# I3C_Slaves.net
KiCad netlist of a schematic drawn in Altium Designer
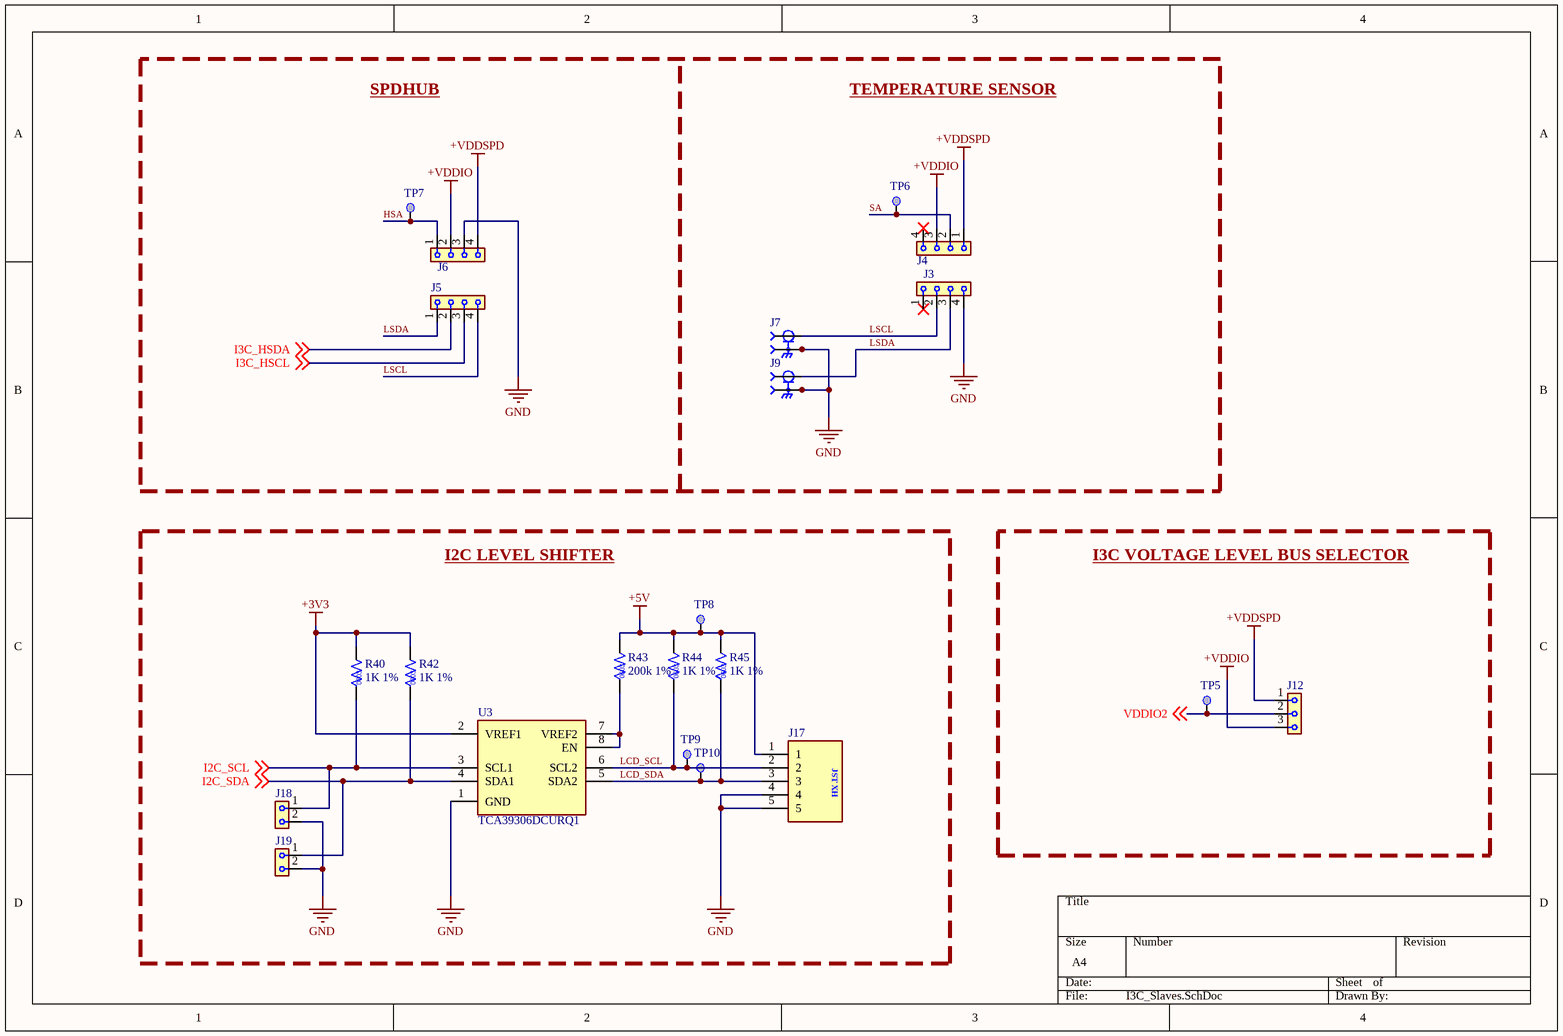
[diagram p0: I3C_Slaves.SchDoc]

(export (version "E")
  (design (tool "Eeschema 10.0.6"))
  (components
    (comp (ref "J3")
      (value "61300411821")
      (footprint "61300411821")
      (description "2.54mm Scket Header 4 pins")
      (fields (field (name "MANUFACTURER") "Wurth Elektronik"))
      (libsource (lib "DDR5_Nucleo_Shield_Symbols") (part "61300411821"))
    )
    (comp (ref "J4")
      (value "61300411821")
      (footprint "61300411821")
      (description "2.54mm Scket Header 4 pins")
      (fields (field (name "MANUFACTURER") "Wurth Elektronik"))
      (libsource (lib "") (part "61300411821_2"))
    )
    (comp (ref "J5")
      (value "61300411821")
      (footprint "61300411821")
      (description "2.54mm Scket Header 4 pins")
      (fields (field (name "MANUFACTURER") "Wurth Elektronik"))
      (libsource (lib "DDR5_Nucleo_Shield_Symbols") (part "61300411821"))
    )
    (comp (ref "J6")
      (value "61300411821")
      (footprint "61300411821")
      (description "2.54mm Scket Header 4 pins")
      (fields (field (name "MANUFACTURER") "Wurth Elektronik"))
      (libsource (lib "") (part "61300411821_1"))
    )
    (comp (ref "J7")
      (value "MMCX-J-P-H-ST-TH1")
      (footprint "SAMTEC_MMCX-J-P-H-ST-TH1")
      (description "RF Connectors / Coaxial Connectors 50 OHM MMCX JACK OR PLUG")
      (fields (field (name "MANUFACTURER") "Samtec Inc."))
      (libsource (lib "DDR5_Nucleo_Shield_Symbols") (part "MMCX-J-P-H-ST-TH1"))
    )
    (comp (ref "J9")
      (value "MMCX-J-P-H-ST-TH1")
      (footprint "SAMTEC_MMCX-J-P-H-ST-TH1")
      (description "RF Connectors / Coaxial Connectors 50 OHM MMCX JACK OR PLUG")
      (fields (field (name "MANUFACTURER") "Samtec Inc."))
      (libsource (lib "DDR5_Nucleo_Shield_Symbols") (part "MMCX-J-P-H-ST-TH1"))
    )
    (comp (ref "J12")
      (value "TSW-103-07-F-S")
      (footprint "HEADER/VERT/1X3/M/P2.54")
      (description "Pin Header, Unshrouded, Board-to-Board, 2.54 mm, 1 Rows, 3 Contacts, Through Hole, TSW")
      (fields (field (name "MANUFACTURER") "SAMTEC"))
      (libsource (lib "DDR5_Nucleo_Shield_Symbols") (part "TSW-103-07-F-S"))
    )
    (comp (ref "J17")
      (value "B5B-XH-A(LF)(SN)")
      (footprint "JST_XH_5V")
      (description "Alojamientos de cables y cabecera XH HEADER (TOP)")
      (fields (field (name "MANUFACTURER") "JST"))
      (libsource (lib "DDR5_Nucleo_Shield_Symbols") (part "B5B-XH-A(LF)(SN)"))
    )
    (comp (ref "J18")
      (value "TSW-102-07-F-S")
      (footprint "HEADER/VERT/1X2/M/P2.54")
      (description "Alojamientos de cables y cabecera 2.54MM CLASSIC PCB HDR STRIP")
      (fields (field (name "MANUFACTURER") "SAMTEC"))
      (libsource (lib "DDR5_Nucleo_Shield_Symbols") (part "TSW-102-07-F-S"))
    )
    (comp (ref "J19")
      (value "TSW-102-07-F-S")
      (footprint "HEADER/VERT/1X2/M/P2.54")
      (description "Alojamientos de cables y cabecera 2.54MM CLASSIC PCB HDR STRIP")
      (fields (field (name "MANUFACTURER") "SAMTEC"))
      (libsource (lib "DDR5_Nucleo_Shield_Symbols") (part "TSW-102-07-F-S"))
    )
    (comp (ref "R40")
      (value "1K 1%")
      (footprint "CC/NM 0603")
      (fields
        (field (name "MANUFACTURER") "YAGEO")
        (field (name "MANUFACTURER PART NUMBER") "RT0603BRD101KL")
      )
      (libsource (lib "DDR5_Nucleo_Shield_Symbols") (part "RT0603BRD101KL"))
    )
    (comp (ref "R42")
      (value "1K 1%")
      (footprint "CC/NM 0603")
      (fields
        (field (name "MANUFACTURER") "YAGEO")
        (field (name "MANUFACTURER PART NUMBER") "RT0603BRD101KL")
      )
      (libsource (lib "DDR5_Nucleo_Shield_Symbols") (part "RT0603BRD101KL"))
    )
    (comp (ref "R43")
      (value "200k 1%")
      (footprint "CC/NM 0603")
      (description "Resistores de película gruesa - SMD D11/CRCW0603-P 50 200K 1% ET1 e3")
      (fields (field (name "MANUFACTURER PART NUMBER") "CRCW0603200KFHEAP"))
      (libsource (lib "DDR5_Nucleo_Shield_Symbols") (part "CRCW0603200KFHEAP"))
    )
    (comp (ref "R44")
      (value "1K 1%")
      (footprint "CC/NM 0603")
      (fields
        (field (name "MANUFACTURER") "YAGEO")
        (field (name "MANUFACTURER PART NUMBER") "RT0603BRD101KL")
      )
      (libsource (lib "DDR5_Nucleo_Shield_Symbols") (part "RT0603BRD101KL"))
    )
    (comp (ref "R45")
      (value "1K 1%")
      (footprint "CC/NM 0603")
      (fields
        (field (name "MANUFACTURER") "YAGEO")
        (field (name "MANUFACTURER PART NUMBER") "RT0603BRD101KL")
      )
      (libsource (lib "DDR5_Nucleo_Shield_Symbols") (part "RT0603BRD101KL"))
    )
    (comp (ref "TP5")
      (value "Test Point")
      (footprint "TP_SMD_1MM")
      (description "Test Point 1mm")
      (fields
        (field (name "INTERNAL_PART_NUMBER") "MCD-00074")
        (field (name "MANUFACTURER_PART_NUMBER") "n/a")
      )
      (libsource (lib "DDR5_Nucleo_Shield_Symbols") (part "Test_Point_1mm"))
    )
    (comp (ref "TP6")
      (value "Test Point")
      (footprint "TP_SMD_1MM")
      (description "Test Point 1mm")
      (fields
        (field (name "INTERNAL_PART_NUMBER") "MCD-00074")
        (field (name "MANUFACTURER_PART_NUMBER") "n/a")
      )
      (libsource (lib "DDR5_Nucleo_Shield_Symbols") (part "Test_Point_1mm"))
    )
    (comp (ref "TP7")
      (value "Test Point")
      (footprint "TP_SMD_1MM")
      (description "Test Point 1mm")
      (fields
        (field (name "INTERNAL_PART_NUMBER") "MCD-00074")
        (field (name "MANUFACTURER_PART_NUMBER") "n/a")
      )
      (libsource (lib "DDR5_Nucleo_Shield_Symbols") (part "Test_Point_1mm"))
    )
    (comp (ref "TP8")
      (value "Test Point")
      (footprint "TP_SMD_1MM")
      (description "Test Point 1mm")
      (fields
        (field (name "INTERNAL_PART_NUMBER") "MCD-00074")
        (field (name "MANUFACTURER_PART_NUMBER") "n/a")
      )
      (libsource (lib "DDR5_Nucleo_Shield_Symbols") (part "Test_Point_1mm"))
    )
    (comp (ref "TP9")
      (value "Test Point")
      (footprint "TP_SMD_1MM")
      (description "Test Point 1mm")
      (fields
        (field (name "INTERNAL_PART_NUMBER") "MCD-00074")
        (field (name "MANUFACTURER_PART_NUMBER") "n/a")
      )
      (libsource (lib "DDR5_Nucleo_Shield_Symbols") (part "Test_Point_1mm"))
    )
    (comp (ref "TP10")
      (value "Test Point")
      (footprint "TP_SMD_1MM")
      (description "Test Point 1mm")
      (fields
        (field (name "INTERNAL_PART_NUMBER") "MCD-00074")
        (field (name "MANUFACTURER_PART_NUMBER") "n/a")
      )
      (libsource (lib "DDR5_Nucleo_Shield_Symbols") (part "Test_Point_1mm"))
    )
    (comp (ref "U3")
      (value "TCA39306DCURQ1")
      (footprint "SOP50P310X90-8N")
      (fields (field (name "MANUFACTURER") "TI"))
      (libsource (lib "altium-import") (part "root_0_TCA39306DCURQ1_"))
    )
  )
  (nets
    (net (code "1") (name "+3V3") (class "Default")
      (node (ref "R40") (pin "2") (pinfunction "2_2") (pintype "passive"))
      (node (ref "R42") (pin "2") (pinfunction "2_2") (pintype "passive"))
      (node (ref "U3") (pin "2") (pinfunction "VREF1_2") (pintype "passive"))
    )
    (net (code "2") (name "+5V") (class "Default")
      (node (ref "J17") (pin "1") (pinfunction "1_1") (pintype "passive"))
      (node (ref "R43") (pin "2") (pinfunction "2_2") (pintype "passive"))
      (node (ref "R44") (pin "2") (pinfunction "2_2") (pintype "passive"))
      (node (ref "R45") (pin "2") (pinfunction "2_2") (pintype "passive"))
      (node (ref "TP8") (pin "1") (pinfunction "1_1") (pintype "passive"))
    )
    (net (code "3") (name "+VDDIO") (class "Default")
      (node (ref "J12") (pin "3") (pinfunction "3_3") (pintype "passive"))
      (node (ref "J4") (pin "3") (pinfunction "3_3") (pintype "passive"))
      (node (ref "J6") (pin "2") (pinfunction "2_2") (pintype "passive"))
    )
    (net (code "4") (name "+VDDSPD") (class "Default")
      (node (ref "J12") (pin "1") (pinfunction "1_1") (pintype "passive"))
      (node (ref "J4") (pin "1") (pinfunction "1_1") (pintype "passive"))
      (node (ref "J6") (pin "4") (pinfunction "4_4") (pintype "passive"))
    )
    (net (code "5") (name "/HSA") (class "Default")
      (node (ref "J6") (pin "1") (pinfunction "1_1") (pintype "passive"))
      (node (ref "TP7") (pin "1") (pinfunction "1_1") (pintype "passive"))
    )
    (net (code "6") (name "/LCD_SCL") (class "Default")
      (node (ref "J17") (pin "2") (pinfunction "2_2") (pintype "passive"))
      (node (ref "R44") (pin "1") (pinfunction "1_1") (pintype "passive"))
      (node (ref "TP9") (pin "1") (pinfunction "1_1") (pintype "passive"))
      (node (ref "U3") (pin "6") (pinfunction "SCL2_6") (pintype "passive"))
    )
    (net (code "7") (name "/LCD_SDA") (class "Default")
      (node (ref "J17") (pin "3") (pinfunction "3_3") (pintype "passive"))
      (node (ref "R45") (pin "1") (pinfunction "1_1") (pintype "passive"))
      (node (ref "TP10") (pin "1") (pinfunction "1_1") (pintype "passive"))
      (node (ref "U3") (pin "5") (pinfunction "SDA2_5") (pintype "passive"))
    )
    (net (code "8") (name "/LSCL") (class "Default")
      (node (ref "J3") (pin "2") (pinfunction "2_2") (pintype "passive"))
      (node (ref "J5") (pin "4") (pinfunction "4_4") (pintype "passive"))
      (node (ref "J7") (pin "1") (pinfunction "1_1") (pintype "passive"))
    )
    (net (code "9") (name "/LSDA") (class "Default")
      (node (ref "J3") (pin "3") (pinfunction "3_3") (pintype "passive"))
      (node (ref "J5") (pin "1") (pinfunction "1_1") (pintype "passive"))
      (node (ref "J9") (pin "1") (pinfunction "1_1") (pintype "passive"))
    )
    (net (code "10") (name "/SA") (class "Default")
      (node (ref "J4") (pin "2") (pinfunction "2_2") (pintype "passive"))
      (node (ref "TP6") (pin "1") (pinfunction "1_1") (pintype "passive"))
    )
    (net (code "11") (name "GND") (class "Default")
      (node (ref "J17") (pin "4") (pinfunction "4_4") (pintype "passive"))
      (node (ref "J17") (pin "5") (pinfunction "5_5") (pintype "passive"))
      (node (ref "J18") (pin "2") (pinfunction "2_2") (pintype "passive"))
      (node (ref "J19") (pin "2") (pinfunction "2_2") (pintype "passive"))
      (node (ref "J3") (pin "4") (pinfunction "4_4") (pintype "passive"))
      (node (ref "J6") (pin "3") (pinfunction "3_3") (pintype "passive"))
      (node (ref "J7") (pin "S1") (pinfunction "2_S1") (pintype "passive"))
      (node (ref "J7") (pin "S2") (pinfunction "2_S2") (pintype "passive"))
      (node (ref "J7") (pin "S3") (pinfunction "2_S3") (pintype "passive"))
      (node (ref "J7") (pin "S4") (pinfunction "2_S4") (pintype "passive"))
      (node (ref "J9") (pin "S1") (pinfunction "2_S1") (pintype "passive"))
      (node (ref "J9") (pin "S2") (pinfunction "2_S2") (pintype "passive"))
      (node (ref "J9") (pin "S3") (pinfunction "2_S3") (pintype "passive"))
      (node (ref "J9") (pin "S4") (pinfunction "2_S4") (pintype "passive"))
      (node (ref "U3") (pin "1") (pinfunction "GND_1") (pintype "passive"))
    )
    (net (code "12") (name "I2C_SCL") (class "Default")
      (node (ref "J18") (pin "1") (pinfunction "1_1") (pintype "passive"))
      (node (ref "R40") (pin "1") (pinfunction "1_1") (pintype "passive"))
      (node (ref "U3") (pin "3") (pinfunction "SCL1_3") (pintype "passive"))
    )
    (net (code "13") (name "I2C_SDA") (class "Default")
      (node (ref "J19") (pin "1") (pinfunction "1_1") (pintype "passive"))
      (node (ref "R42") (pin "1") (pinfunction "1_1") (pintype "passive"))
      (node (ref "U3") (pin "4") (pinfunction "SDA1_4") (pintype "passive"))
    )
    (net (code "14") (name "I3C_HSCL") (class "Default")
      (node (ref "J5") (pin "3") (pinfunction "3_3") (pintype "passive"))
    )
    (net (code "15") (name "I3C_HSDA") (class "Default")
      (node (ref "J5") (pin "2") (pinfunction "2_2") (pintype "passive"))
    )
    (net (code "16") (name "Net-(U3-EN)") (class "Default")
      (node (ref "R43") (pin "1") (pinfunction "1_1") (pintype "passive"))
      (node (ref "U3") (pin "7") (pinfunction "VREF2_7") (pintype "passive"))
      (node (ref "U3") (pin "8") (pinfunction "EN_8") (pintype "passive"))
    )
    (net (code "17") (name "VDDIO2") (class "Default")
      (node (ref "J12") (pin "2") (pinfunction "2_2") (pintype "passive"))
      (node (ref "TP5") (pin "1") (pinfunction "1_1") (pintype "passive"))
    )
    (net (code "18") (name "unconnected-(J3-Pad1)") (class "Default")
      (node (ref "J3") (pin "1") (pinfunction "1_1") (pintype "passive+no_connect"))
    )
    (net (code "19") (name "unconnected-(J4-Pad4)") (class "Default")
      (node (ref "J4") (pin "4") (pinfunction "4_4") (pintype "passive+no_connect"))
    )
  )
)
